# LED_Controller.net
KiCad netlist of a schematic drawn in EAGLE
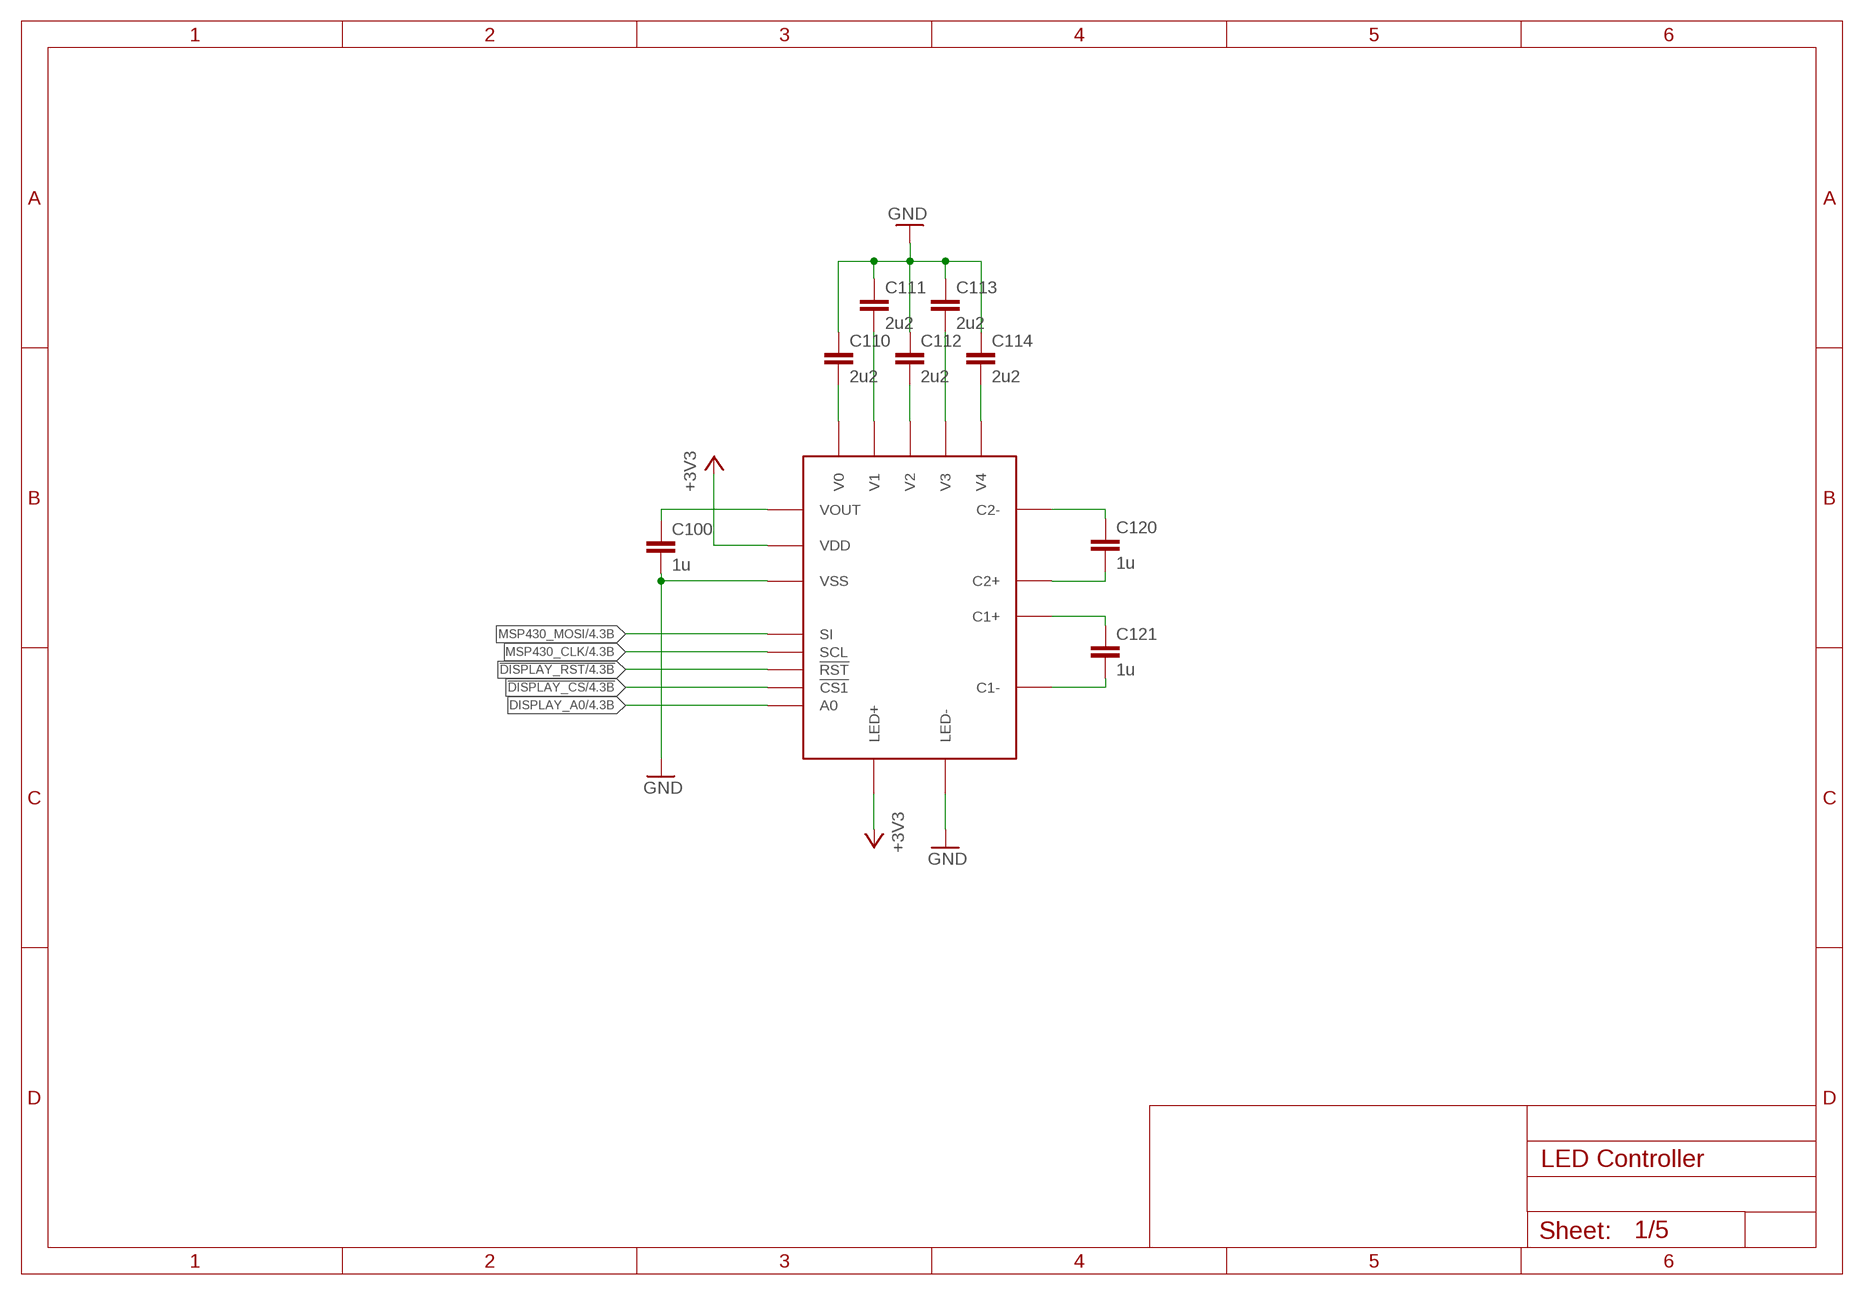
[diagram p0: schematic, sheet 1]
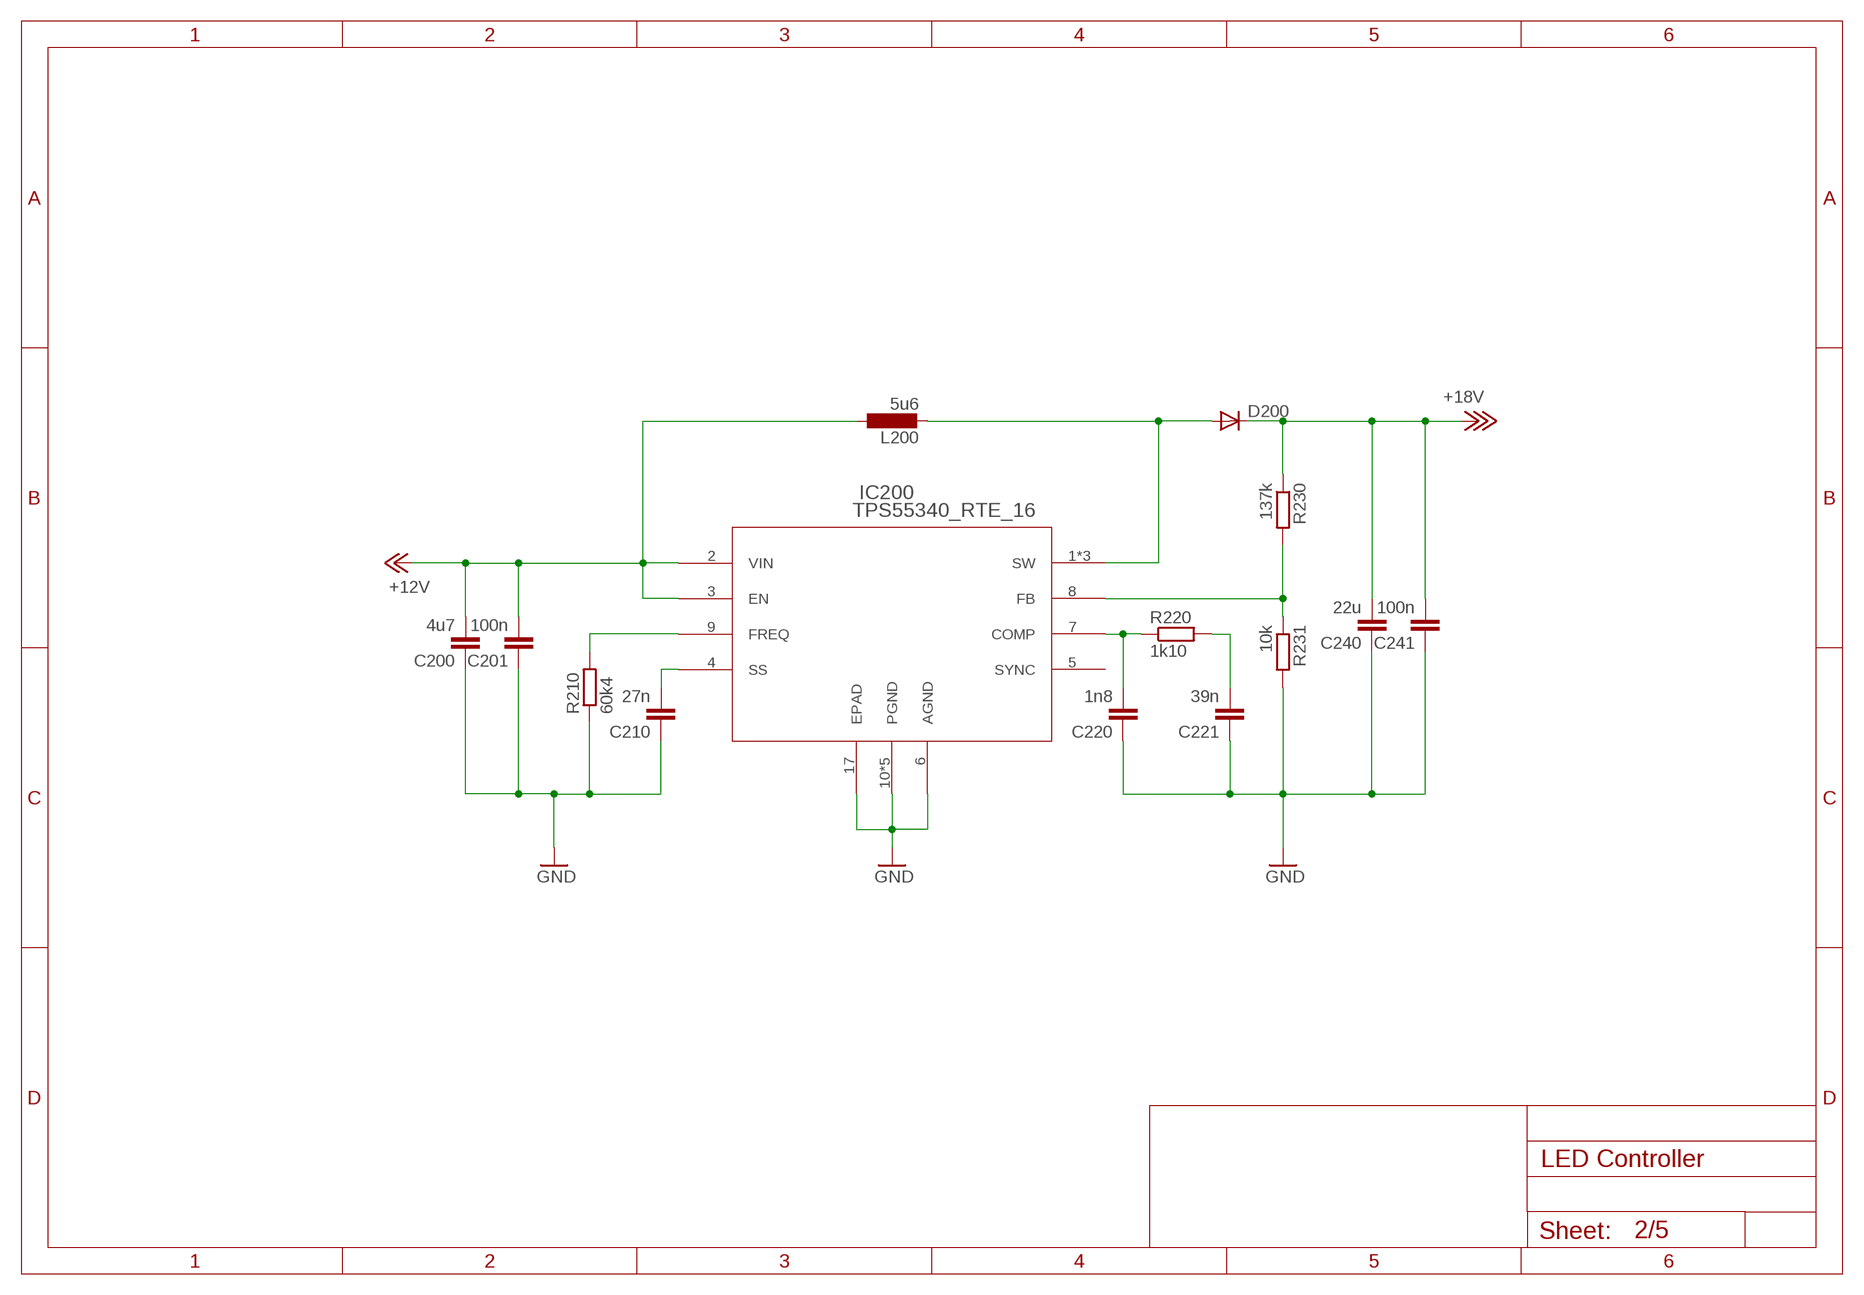
[diagram p1: schematic, sheet 2]
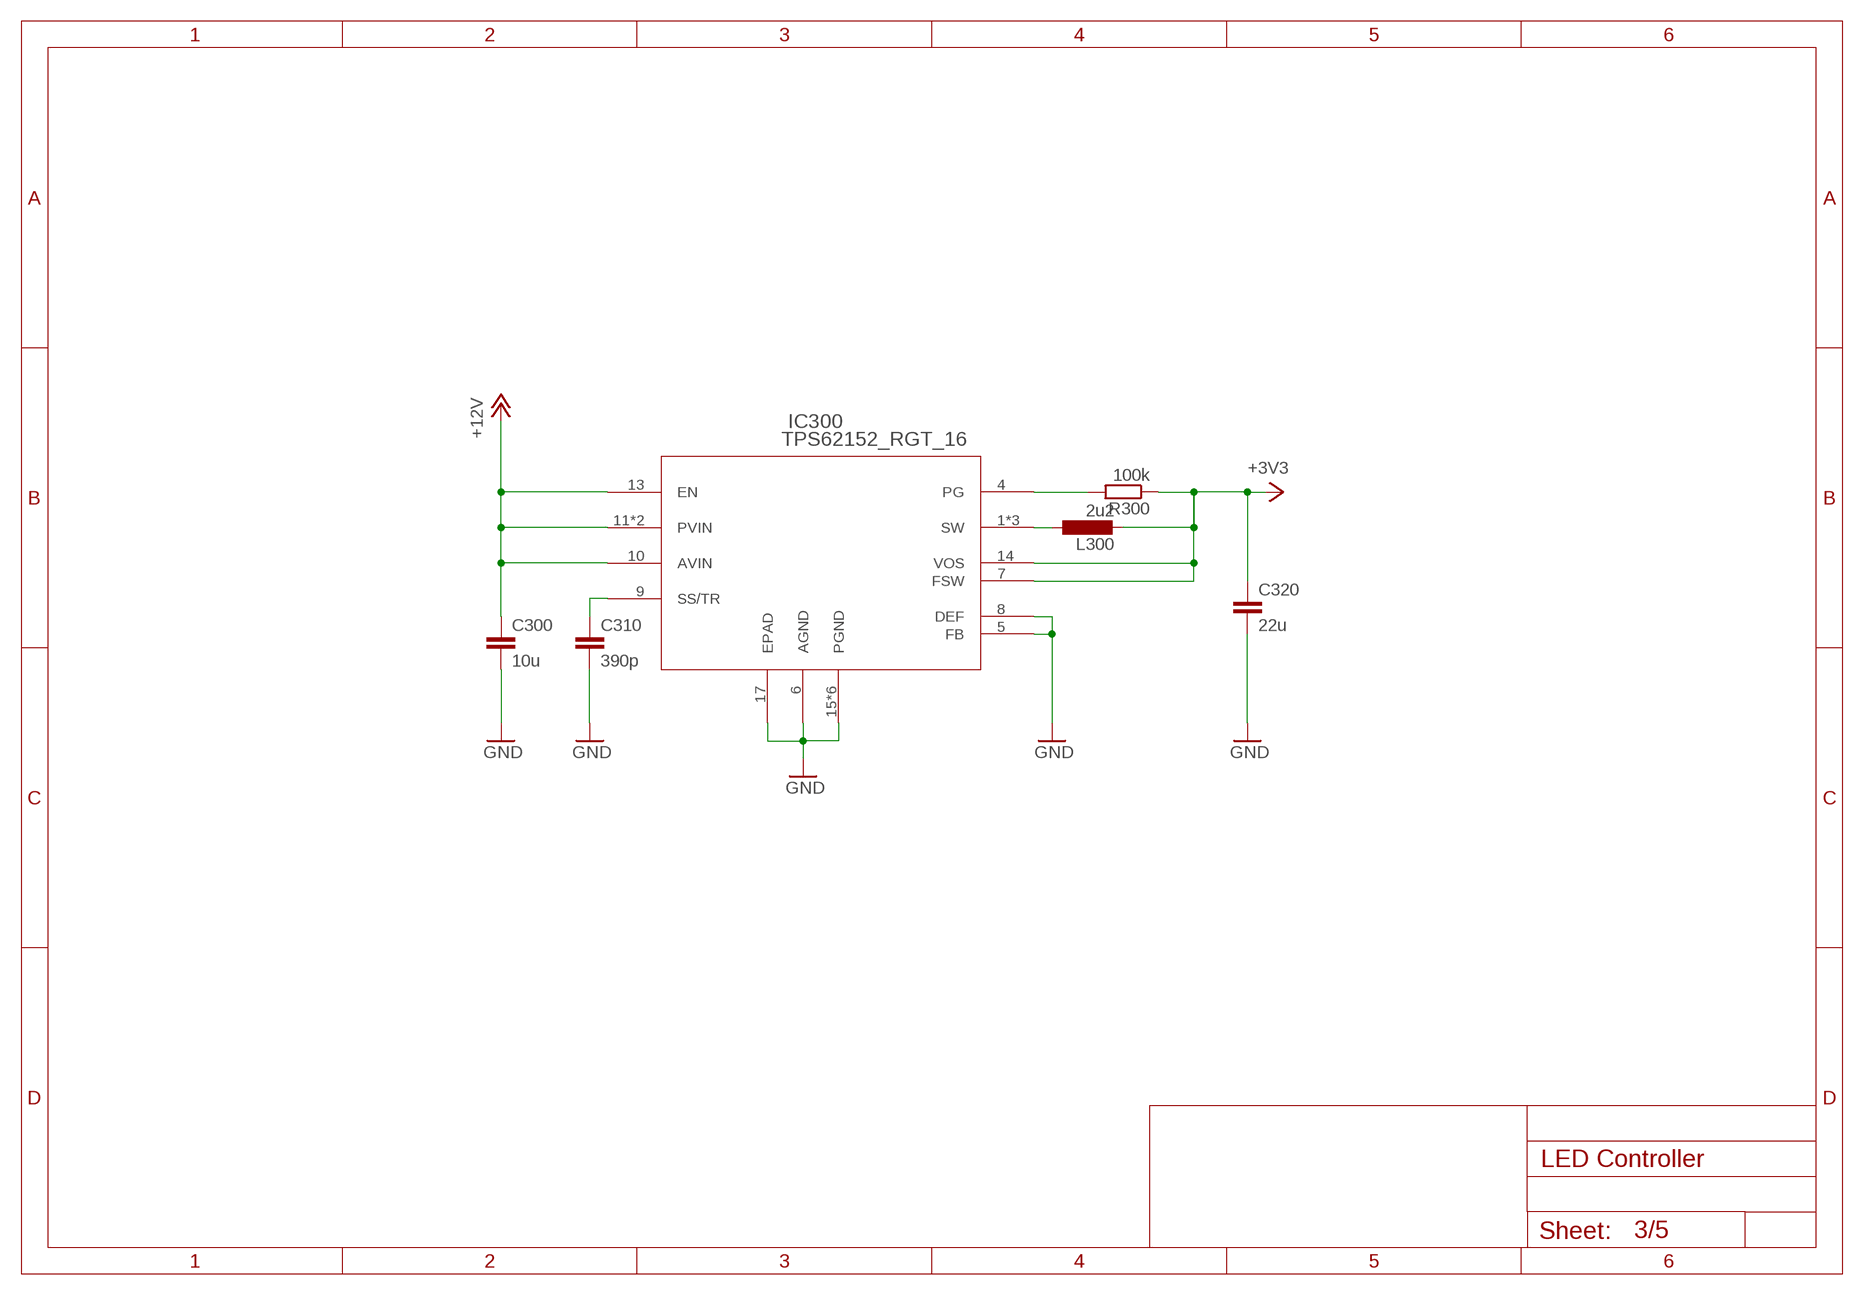
[diagram p2: schematic, sheet 3]
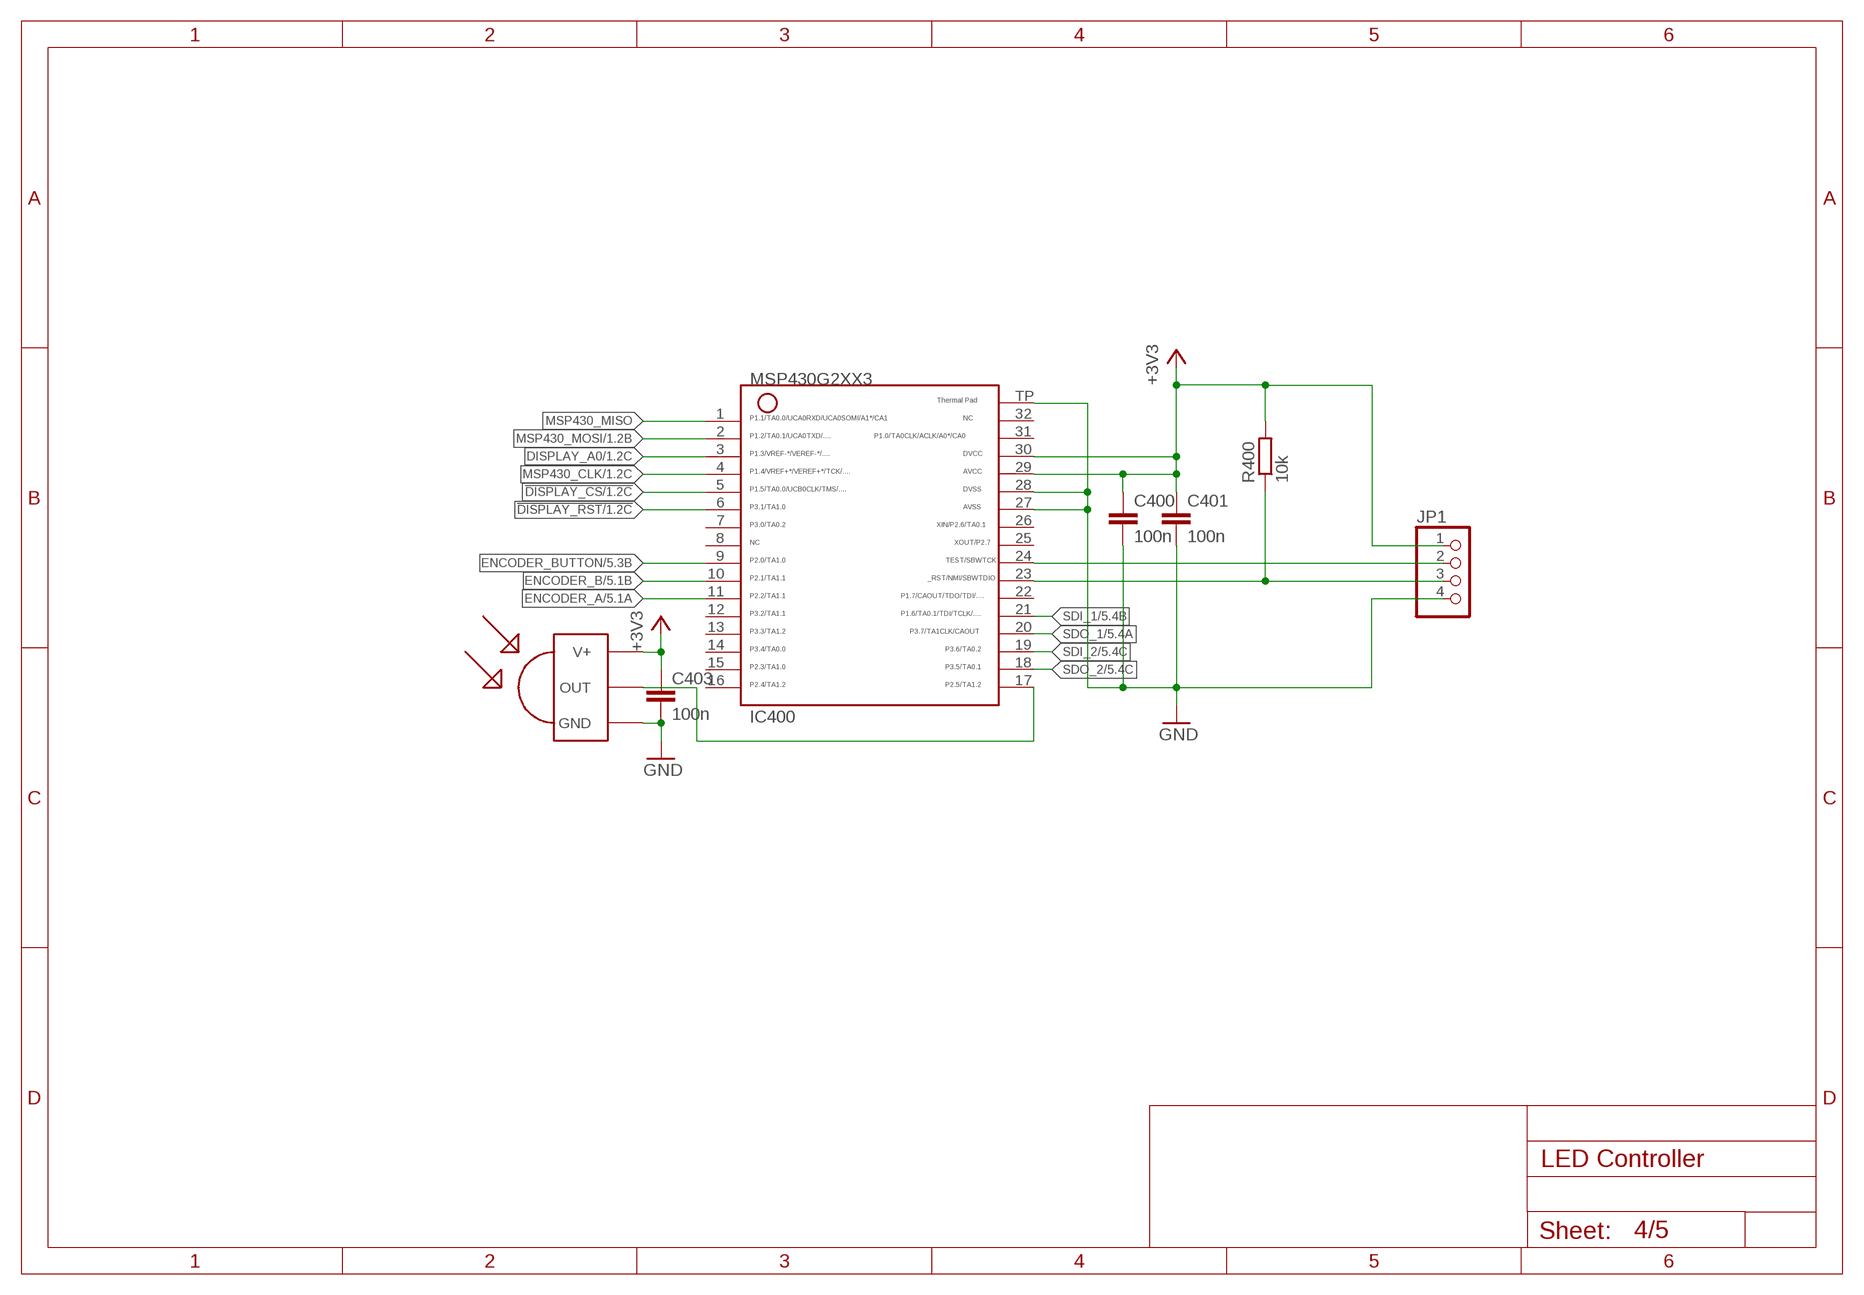
[diagram p3: schematic, sheet 4]
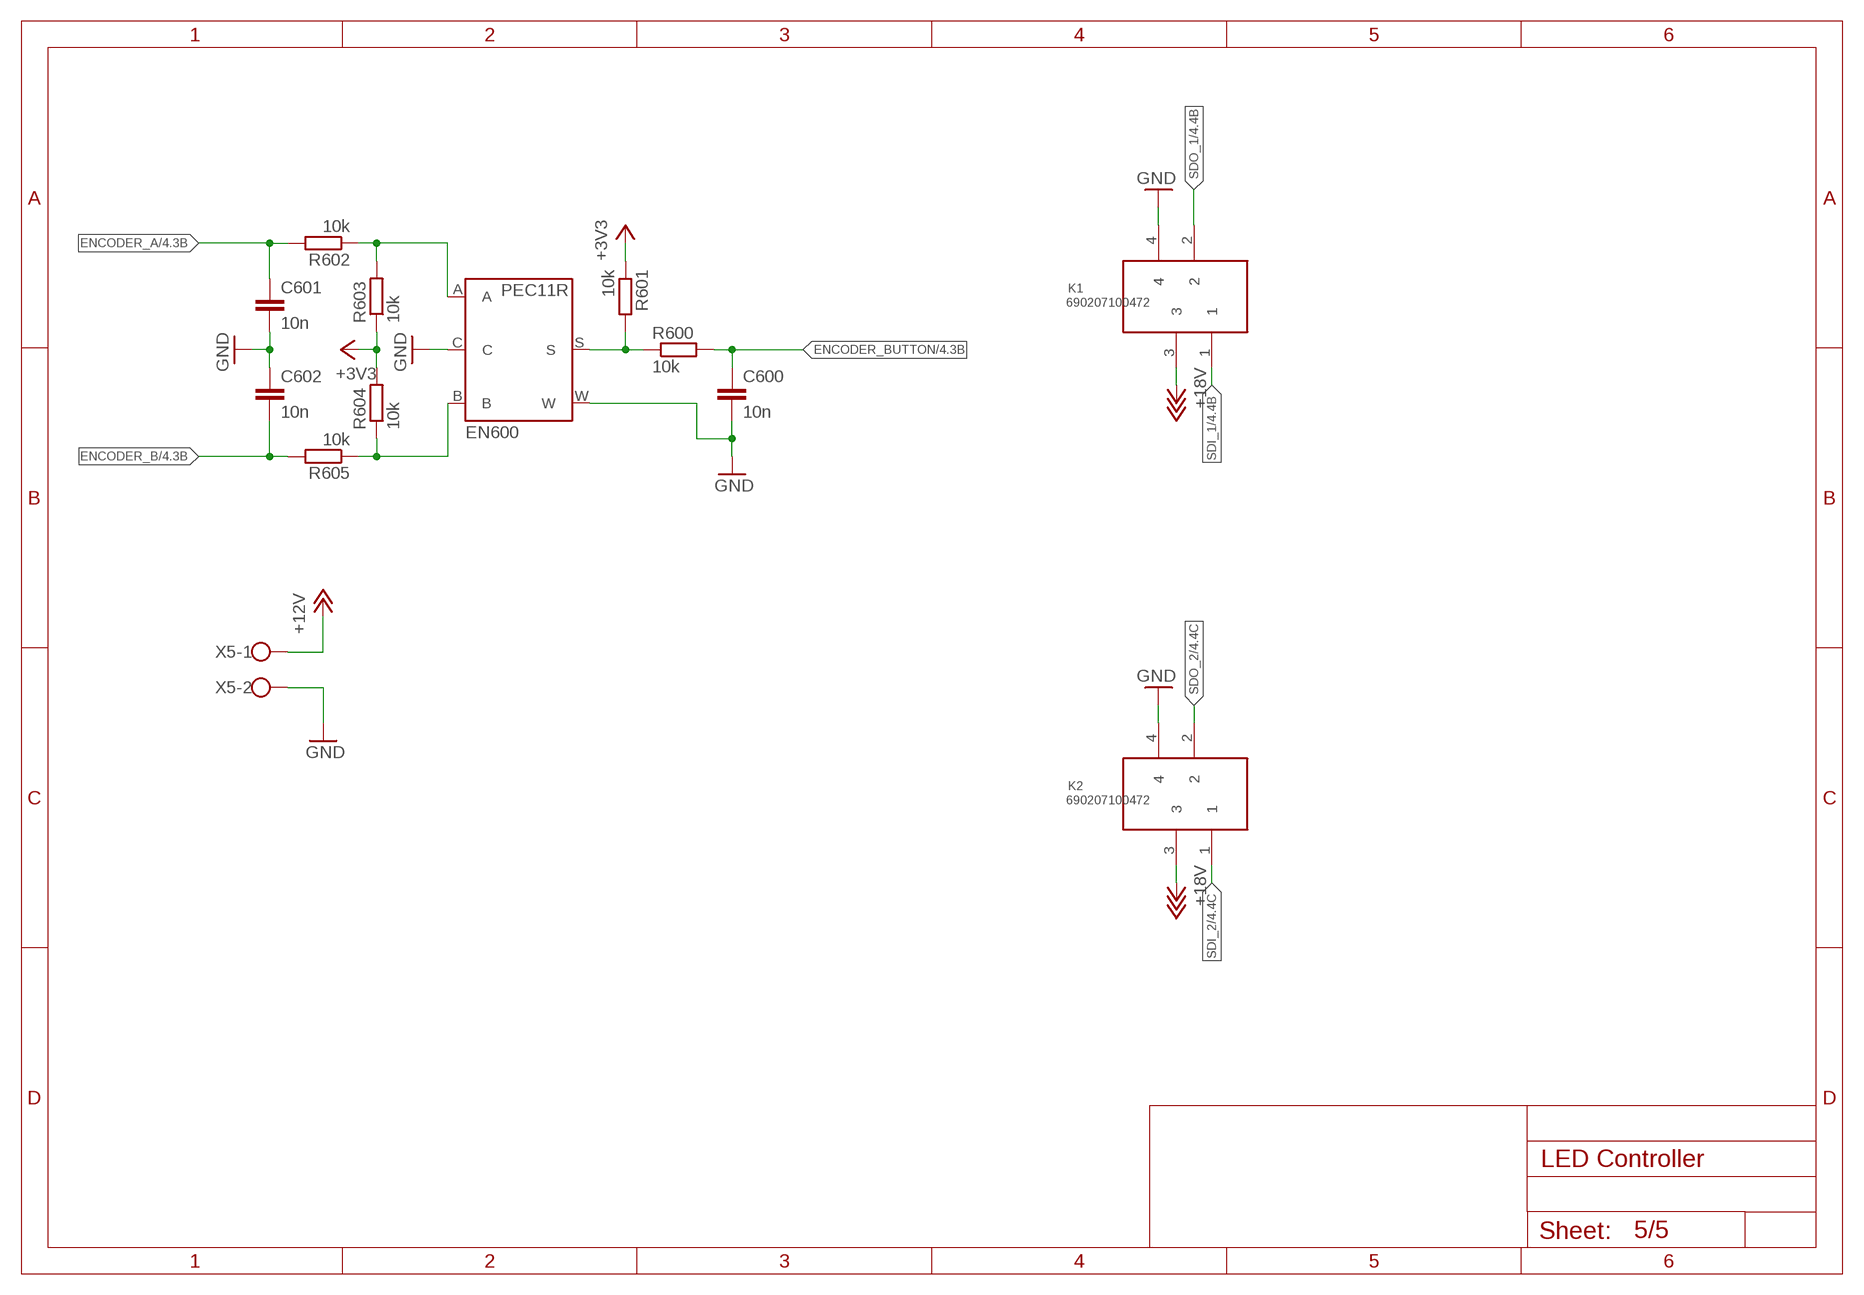
[diagram p4: schematic, sheet 5]

(export (version "E")
  (design (tool "Eeschema 10.0.6"))
  (components
    (comp (ref "C300")
      (value "10u")
      (footprint "eagle-import:C0805")
      (libsource (lib "eagle-import") (part "C-EUC0805"))
    )
    (comp (ref "C310")
      (value "390p")
      (footprint "eagle-import:C0603")
      (libsource (lib "eagle-import") (part "C-EUC0603"))
    )
    (comp (ref "C320")
      (value "22u")
      (footprint "eagle-import:C0805")
      (libsource (lib "eagle-import") (part "C-EUC0805"))
    )
    (comp (ref "IC300")
      (value "TPS62152_RGT_16")
      (footprint "eagle-import:RGT16_1P7X1P7")
      (fields
        (field (name "GENERIC_PART_NUMBER") "TPS62152")
        (field (name "MANUFACTURER") "Texas Instruments")
        (field (name "MANUFACTURER_PART_NUMBER") "tps62152_rgt_16")
      )
      (libsource (lib "eagle-import") (part "TPS62152_RGT_16"))
    )
    (comp (ref "L300")
      (value "2u2")
      (footprint "eagle-import:SDR0403")
      (libsource (lib "eagle-import") (part "L-EUSDR0403"))
    )
    (comp (ref "R300")
      (value "100k")
      (footprint "eagle-import:R0603")
      (libsource (lib "eagle-import") (part "R-EU_R0603"))
    )
    (comp (ref "C100")
      (value "1u")
      (footprint "eagle-import:C0603")
      (libsource (lib "eagle-import") (part "C-EUC0603"))
    )
    (comp (ref "C110")
      (value "2u2")
      (footprint "eagle-import:C0603")
      (libsource (lib "eagle-import") (part "C-EUC0603"))
    )
    (comp (ref "C111")
      (value "2u2")
      (footprint "eagle-import:C0603")
      (libsource (lib "eagle-import") (part "C-EUC0603"))
    )
    (comp (ref "C112")
      (value "2u2")
      (footprint "eagle-import:C0603")
      (libsource (lib "eagle-import") (part "C-EUC0603"))
    )
    (comp (ref "C113")
      (value "2u2")
      (footprint "eagle-import:C0603")
      (libsource (lib "eagle-import") (part "C-EUC0603"))
    )
    (comp (ref "C114")
      (value "2u2")
      (footprint "eagle-import:C0603")
      (libsource (lib "eagle-import") (part "C-EUC0603"))
    )
    (comp (ref "C120")
      (value "1u")
      (footprint "eagle-import:C0603")
      (libsource (lib "eagle-import") (part "C-EUC0603"))
    )
    (comp (ref "C121")
      (value "1u")
      (footprint "eagle-import:C0603")
      (libsource (lib "eagle-import") (part "C-EUC0603"))
    )
    (comp (ref "U$3")
      (value "DISPLAY")
      (footprint "eagle-import:NHD-C12832A1Z-NSW-BBW-3V3")
      (libsource (lib "eagle-import") (part "DISPLAY"))
    )
    (comp (ref "C200")
      (value "4u7")
      (footprint "eagle-import:C1206")
      (libsource (lib "eagle-import") (part "C-EUC1206"))
    )
    (comp (ref "C201")
      (value "100n")
      (footprint "eagle-import:C1206")
      (libsource (lib "eagle-import") (part "C-EUC1206"))
    )
    (comp (ref "C210")
      (value "27n")
      (footprint "eagle-import:C0603")
      (libsource (lib "eagle-import") (part "C-EUC0603"))
    )
    (comp (ref "C220")
      (value "1n8")
      (footprint "eagle-import:C0603")
      (libsource (lib "eagle-import") (part "C-EUC0603"))
    )
    (comp (ref "C221")
      (value "39n")
      (footprint "eagle-import:C0603")
      (libsource (lib "eagle-import") (part "C-EUC0603"))
    )
    (comp (ref "C240")
      (value "22u")
      (footprint "eagle-import:C1210")
      (libsource (lib "eagle-import") (part "C-EUC1210"))
    )
    (comp (ref "C241")
      (value "100n")
      (footprint "eagle-import:C1206")
      (libsource (lib "eagle-import") (part "C-EUC1206"))
    )
    (comp (ref "D200")
      (value "DIODE-SMC")
      (footprint "eagle-import:SMC")
      (libsource (lib "eagle-import") (part "DIODE-SMC"))
    )
    (comp (ref "IC200")
      (value "TPS55340_RTE_16")
      (footprint "eagle-import:RTE16")
      (fields (field (name "MANUFACTURER_PART_NUMBER") "tps55340_rte_16"))
      (libsource (lib "eagle-import") (part "TPS55340_RTE_16"))
    )
    (comp (ref "L200")
      (value "5u6")
      (footprint "eagle-import:SRP5030T")
      (libsource (lib "eagle-import") (part "L-EUSRP5030T"))
    )
    (comp (ref "R210")
      (value "60k4")
      (footprint "eagle-import:R0603")
      (libsource (lib "eagle-import") (part "R-EU_R0603"))
    )
    (comp (ref "R220")
      (value "1k10")
      (footprint "eagle-import:R0603")
      (libsource (lib "eagle-import") (part "R-EU_R0603"))
    )
    (comp (ref "R230")
      (value "137k")
      (footprint "eagle-import:R0603")
      (libsource (lib "eagle-import") (part "R-EU_R0603"))
    )
    (comp (ref "R231")
      (value "10k")
      (footprint "eagle-import:R0603")
      (libsource (lib "eagle-import") (part "R-EU_R0603"))
    )
    (comp (ref "C600")
      (value "10n")
      (footprint "eagle-import:C0603")
      (libsource (lib "eagle-import") (part "C-EUC0603"))
    )
    (comp (ref "C601")
      (value "10n")
      (footprint "eagle-import:C0603")
      (libsource (lib "eagle-import") (part "C-EUC0603"))
    )
    (comp (ref "C602")
      (value "10n")
      (footprint "eagle-import:C0603")
      (libsource (lib "eagle-import") (part "C-EUC0603"))
    )
    (comp (ref "EN600")
      (value "PEC11R")
      (footprint "eagle-import:PEC11R")
      (libsource (lib "eagle-import") (part "PEC11R"))
    )
    (comp (ref "K1")
      (value "690207100472")
      (footprint "eagle-import:690207100472")
      (libsource (lib "eagle-import") (part "690207100472"))
    )
    (comp (ref "K2")
      (value "690207100472")
      (footprint "eagle-import:690207100472")
      (libsource (lib "eagle-import") (part "690207100472"))
    )
    (comp (ref "R600")
      (value "10k")
      (footprint "eagle-import:R0603")
      (libsource (lib "eagle-import") (part "R-EU_R0603"))
    )
    (comp (ref "R601")
      (value "10k")
      (footprint "eagle-import:R0603")
      (libsource (lib "eagle-import") (part "R-EU_R0603"))
    )
    (comp (ref "R602")
      (value "10k")
      (footprint "eagle-import:R0603")
      (libsource (lib "eagle-import") (part "R-EU_R0603"))
    )
    (comp (ref "R603")
      (value "10k")
      (footprint "eagle-import:R0603")
      (libsource (lib "eagle-import") (part "R-EU_R0603"))
    )
    (comp (ref "R604")
      (value "10k")
      (footprint "eagle-import:R0603")
      (libsource (lib "eagle-import") (part "R-EU_R0603"))
    )
    (comp (ref "R605")
      (value "10k")
      (footprint "eagle-import:R0603")
      (libsource (lib "eagle-import") (part "R-EU_R0603"))
    )
    (comp (ref "X5")
      (value "W237-102")
      (footprint "eagle-import:W237-102")
      (fields (field (name "MPN") "237-102"))
      (libsource (lib "eagle-import") (part "W237-102"))
    )
    (comp (ref "C400")
      (value "100n")
      (footprint "eagle-import:C0603")
      (libsource (lib "eagle-import") (part "C-EUC0603"))
    )
    (comp (ref "C401")
      (value "100n")
      (footprint "eagle-import:C0603")
      (libsource (lib "eagle-import") (part "C-EUC0603"))
    )
    (comp (ref "C403")
      (value "100n")
      (footprint "eagle-import:C0603")
      (libsource (lib "eagle-import") (part "C-EUC0603"))
    )
    (comp (ref "IC400")
      (value "G2XX3---RHB32")
      (footprint "eagle-import:RHB32")
      (libsource (lib "eagle-import") (part "G2XX3---RHB32"))
    )
    (comp (ref "JP1")
      (value "PINHD-1X4")
      (footprint "eagle-import:1X04")
      (libsource (lib "eagle-import") (part "PINHD-1X4"))
    )
    (comp (ref "R400")
      (value "10k")
      (footprint "eagle-import:R0603")
      (libsource (lib "eagle-import") (part "R-EU_R0603"))
    )
    (comp (ref "U$1")
      (value "TSOP1738")
      (footprint "eagle-import:TSOP17XX")
      (libsource (lib "eagle-import") (part "TSOP1738"))
    )
  )
  (nets
    (net (code "1") (name "+3V3") (class "Default")
      (node (ref "C320") (pin "1") (pinfunction "1_1") (pintype "passive"))
      (node (ref "C400") (pin "1") (pinfunction "1_1") (pintype "passive"))
      (node (ref "C401") (pin "1") (pinfunction "1_1") (pintype "passive"))
      (node (ref "C403") (pin "1") (pinfunction "1_1") (pintype "passive"))
      (node (ref "IC300") (pin "14") (pinfunction "VOS_14") (pintype "input"))
      (node (ref "IC300") (pin "7") (pinfunction "FSW_7") (pintype "input"))
      (node (ref "IC400") (pin "29") (pinfunction "29_29") (pintype "bidirectional"))
      (node (ref "IC400") (pin "30") (pinfunction "30_30") (pintype "bidirectional"))
      (node (ref "JP1") (pin "1") (pinfunction "1_1") (pintype "passive"))
      (node (ref "L300") (pin "V_2") (pinfunction "2_V_2") (pintype "passive"))
      (node (ref "R300") (pin "1") (pinfunction "1_1") (pintype "passive"))
      (node (ref "R400") (pin "2") (pinfunction "2_2") (pintype "passive"))
      (node (ref "R601") (pin "1") (pinfunction "1_1") (pintype "passive"))
      (node (ref "R603") (pin "1") (pinfunction "1_1") (pintype "passive"))
      (node (ref "R604") (pin "2") (pinfunction "2_2") (pintype "passive"))
      (node (ref "U$1") (pin "V+") (pinfunction "V+_V+") (pintype "bidirectional"))
      (node (ref "U$3") (pin "A") (pinfunction "LED+_A") (pintype "passive"))
      (node (ref "U$3") (pin "P12") (pinfunction "VDD_P12") (pintype "passive"))
    )
    (net (code "2") (name "+12V") (class "Default")
      (node (ref "C200") (pin "2") (pinfunction "2_2") (pintype "passive"))
      (node (ref "C201") (pin "2") (pinfunction "2_2") (pintype "passive"))
      (node (ref "C300") (pin "1") (pinfunction "1_1") (pintype "passive"))
      (node (ref "IC200") (pin "2") (pinfunction "VIN_2") (pintype "input"))
      (node (ref "IC200") (pin "3") (pinfunction "EN_3") (pintype "passive"))
      (node (ref "IC300") (pin "10") (pinfunction "AVIN_10") (pintype "input"))
      (node (ref "IC300") (pin "11") (pinfunction "PVIN_11") (pintype "input"))
      (node (ref "IC300") (pin "12") (pinfunction "PVIN_12") (pintype "input"))
      (node (ref "IC300") (pin "13") (pinfunction "EN_13") (pintype "input"))
      (node (ref "L200") (pin "V_1") (pinfunction "1_V_1") (pintype "passive"))
      (node (ref "X5") (pin "1") (pinfunction "KL_1") (pintype "passive"))
    )
    (net (code "3") (name "+18V") (class "Default")
      (node (ref "C240") (pin "2") (pinfunction "2_2") (pintype "passive"))
      (node (ref "C241") (pin "2") (pinfunction "2_2") (pintype "passive"))
      (node (ref "D200") (pin "C") (pinfunction "C_C") (pintype "passive"))
      (node (ref "K1") (pin "3") (pinfunction "3_3") (pintype "passive"))
      (node (ref "K2") (pin "3") (pinfunction "3_3") (pintype "passive"))
      (node (ref "R230") (pin "1") (pinfunction "1_1") (pintype "passive"))
    )
    (net (code "4") (name "DISPLAY_A0") (class "Default")
      (node (ref "IC400") (pin "3") (pinfunction "3_3") (pintype "bidirectional"))
      (node (ref "U$3") (pin "P15") (pinfunction "A0_P15") (pintype "passive"))
    )
    (net (code "5") (name "ENCODER_A") (class "Default")
      (node (ref "C601") (pin "1") (pinfunction "1_1") (pintype "passive"))
      (node (ref "IC400") (pin "11") (pinfunction "11_11") (pintype "bidirectional"))
      (node (ref "R602") (pin "2") (pinfunction "2_2") (pintype "passive"))
    )
    (net (code "6") (name "ENCODER_B") (class "Default")
      (node (ref "C602") (pin "2") (pinfunction "2_2") (pintype "passive"))
      (node (ref "IC400") (pin "10") (pinfunction "10_10") (pintype "bidirectional"))
      (node (ref "R605") (pin "2") (pinfunction "2_2") (pintype "passive"))
    )
    (net (code "7") (name "ENCODER_BUTTON") (class "Default")
      (node (ref "C600") (pin "1") (pinfunction "1_1") (pintype "passive"))
      (node (ref "IC400") (pin "9") (pinfunction "9_9") (pintype "bidirectional"))
      (node (ref "R600") (pin "2") (pinfunction "2_2") (pintype "passive"))
    )
    (net (code "8") (name "GND") (class "Default")
      (node (ref "C100") (pin "2") (pinfunction "2_2") (pintype "passive"))
      (node (ref "C110") (pin "1") (pinfunction "1_1") (pintype "passive"))
      (node (ref "C111") (pin "1") (pinfunction "1_1") (pintype "passive"))
      (node (ref "C112") (pin "1") (pinfunction "1_1") (pintype "passive"))
      (node (ref "C113") (pin "1") (pinfunction "1_1") (pintype "passive"))
      (node (ref "C114") (pin "1") (pinfunction "1_1") (pintype "passive"))
      (node (ref "C200") (pin "1") (pinfunction "1_1") (pintype "passive"))
      (node (ref "C201") (pin "1") (pinfunction "1_1") (pintype "passive"))
      (node (ref "C210") (pin "1") (pinfunction "1_1") (pintype "passive"))
      (node (ref "C220") (pin "1") (pinfunction "1_1") (pintype "passive"))
      (node (ref "C221") (pin "1") (pinfunction "1_1") (pintype "passive"))
      (node (ref "C240") (pin "1") (pinfunction "1_1") (pintype "passive"))
      (node (ref "C241") (pin "1") (pinfunction "1_1") (pintype "passive"))
      (node (ref "C300") (pin "2") (pinfunction "2_2") (pintype "passive"))
      (node (ref "C310") (pin "2") (pinfunction "2_2") (pintype "passive"))
      (node (ref "C320") (pin "2") (pinfunction "2_2") (pintype "passive"))
      (node (ref "C400") (pin "2") (pinfunction "2_2") (pintype "passive"))
      (node (ref "C401") (pin "2") (pinfunction "2_2") (pintype "passive"))
      (node (ref "C403") (pin "2") (pinfunction "2_2") (pintype "passive"))
      (node (ref "C600") (pin "2") (pinfunction "2_2") (pintype "passive"))
      (node (ref "C601") (pin "2") (pinfunction "2_2") (pintype "passive"))
      (node (ref "C602") (pin "1") (pinfunction "1_1") (pintype "passive"))
      (node (ref "EN600") (pin "C") (pinfunction "C_C") (pintype "bidirectional"))
      (node (ref "EN600") (pin "W") (pinfunction "W_W") (pintype "bidirectional"))
      (node (ref "IC200") (pin "10") (pinfunction "PGND_10") (pintype "power_in"))
      (node (ref "IC200") (pin "11") (pinfunction "PGND_11") (pintype "power_in"))
      (node (ref "IC200") (pin "12") (pinfunction "PGND_12") (pintype "power_in"))
      (node (ref "IC200") (pin "13") (pinfunction "PGND_13") (pintype "power_in"))
      (node (ref "IC200") (pin "14") (pinfunction "PGND_14") (pintype "power_in"))
      (node (ref "IC200") (pin "17") (pinfunction "EPAD_17") (pintype "passive"))
      (node (ref "IC200") (pin "6") (pinfunction "AGND_6") (pintype "power_in"))
      (node (ref "IC300") (pin "15") (pinfunction "PGND_15") (pintype "power_in"))
      (node (ref "IC300") (pin "16") (pinfunction "PGND_16") (pintype "power_in"))
      (node (ref "IC300") (pin "17") (pinfunction "EPAD_17") (pintype "passive"))
      (node (ref "IC300") (pin "5") (pinfunction "FB_5") (pintype "input"))
      (node (ref "IC300") (pin "6") (pinfunction "AGND_6") (pintype "power_in"))
      (node (ref "IC300") (pin "8") (pinfunction "DEF_8") (pintype "input"))
      (node (ref "IC300") (pin "V") (pinfunction "PGND_V") (pintype "power_in"))
      (node (ref "IC300") (pin "V_1") (pinfunction "PGND_V_1") (pintype "power_in"))
      (node (ref "IC300") (pin "V_2") (pinfunction "PGND_V_2") (pintype "power_in"))
      (node (ref "IC300") (pin "V_3") (pinfunction "PGND_V_3") (pintype "power_in"))
      (node (ref "IC400") (pin "27") (pinfunction "27_27") (pintype "bidirectional"))
      (node (ref "IC400") (pin "28") (pinfunction "28_28") (pintype "bidirectional"))
      (node (ref "IC400") (pin "TP") (pinfunction "TP_TP") (pintype "bidirectional"))
      (node (ref "JP1") (pin "4") (pinfunction "4_4") (pintype "passive"))
      (node (ref "K1") (pin "4") (pinfunction "4_4") (pintype "passive"))
      (node (ref "K2") (pin "4") (pinfunction "4_4") (pintype "passive"))
      (node (ref "R210") (pin "1") (pinfunction "1_1") (pintype "passive"))
      (node (ref "R231") (pin "2") (pinfunction "2_2") (pintype "passive"))
      (node (ref "U$1") (pin "GND") (pinfunction "GND_GND") (pintype "bidirectional"))
      (node (ref "U$3") (pin "K") (pinfunction "LED-_K") (pintype "passive"))
      (node (ref "U$3") (pin "P11") (pinfunction "VSS_P11") (pintype "passive"))
      (node (ref "X5") (pin "2") (pinfunction "KL_2") (pintype "passive"))
    )
    (net (code "9") (name "MSP430_CLK") (class "Default")
      (node (ref "IC400") (pin "4") (pinfunction "4_4") (pintype "bidirectional"))
      (node (ref "U$3") (pin "P14") (pinfunction "SCL_P14") (pintype "passive"))
    )
    (net (code "10") (name "MSP430_MISO") (class "Default")
      (node (ref "IC400") (pin "1") (pinfunction "1_1") (pintype "bidirectional"))
    )
    (net (code "11") (name "MSP430_MOSI") (class "Default")
      (node (ref "IC400") (pin "2") (pinfunction "2_2") (pintype "bidirectional"))
      (node (ref "U$3") (pin "P13") (pinfunction "SI_P13") (pintype "passive"))
    )
    (net (code "12") (name "Net-(C221-Pad2)") (class "Default")
      (node (ref "C221") (pin "2") (pinfunction "2_2") (pintype "passive"))
      (node (ref "R220") (pin "2") (pinfunction "2_2") (pintype "passive"))
    )
    (net (code "13") (name "Net-(EN600-PadA)") (class "Default")
      (node (ref "EN600") (pin "A") (pinfunction "A_A") (pintype "bidirectional"))
      (node (ref "R602") (pin "1") (pinfunction "1_1") (pintype "passive"))
      (node (ref "R603") (pin "2") (pinfunction "2_2") (pintype "passive"))
    )
    (net (code "14") (name "Net-(EN600-PadB)") (class "Default")
      (node (ref "EN600") (pin "B") (pinfunction "B_B") (pintype "bidirectional"))
      (node (ref "R604") (pin "1") (pinfunction "1_1") (pintype "passive"))
      (node (ref "R605") (pin "1") (pinfunction "1_1") (pintype "passive"))
    )
    (net (code "15") (name "Net-(EN600-PadS)") (class "Default")
      (node (ref "EN600") (pin "S") (pinfunction "S_S") (pintype "bidirectional"))
      (node (ref "R600") (pin "1") (pinfunction "1_1") (pintype "passive"))
      (node (ref "R601") (pin "2") (pinfunction "2_2") (pintype "passive"))
    )
    (net (code "16") (name "Net-(IC200-COMP)") (class "Default")
      (node (ref "C220") (pin "2") (pinfunction "2_2") (pintype "passive"))
      (node (ref "IC200") (pin "7") (pinfunction "COMP_7") (pintype "passive"))
      (node (ref "R220") (pin "1") (pinfunction "1_1") (pintype "passive"))
    )
    (net (code "17") (name "Net-(IC200-FB)") (class "Default")
      (node (ref "IC200") (pin "8") (pinfunction "FB_8") (pintype "passive"))
      (node (ref "R230") (pin "2") (pinfunction "2_2") (pintype "passive"))
      (node (ref "R231") (pin "1") (pinfunction "1_1") (pintype "passive"))
    )
    (net (code "18") (name "Net-(IC200-FREQ)") (class "Default")
      (node (ref "IC200") (pin "9") (pinfunction "FREQ_9") (pintype "passive"))
      (node (ref "R210") (pin "2") (pinfunction "2_2") (pintype "passive"))
    )
    (net (code "19") (name "Net-(IC200-SS)") (class "Default")
      (node (ref "C210") (pin "2") (pinfunction "2_2") (pintype "passive"))
      (node (ref "IC200") (pin "4") (pinfunction "SS_4") (pintype "passive"))
    )
    (net (code "20") (name "Net-(IC300-PG)") (class "Default")
      (node (ref "IC300") (pin "4") (pinfunction "PG_4") (pintype "output"))
      (node (ref "R300") (pin "2") (pinfunction "2_2") (pintype "passive"))
    )
    (net (code "21") (name "Net-(IC300-SS{slash}TR)") (class "Default")
      (node (ref "C310") (pin "1") (pinfunction "1_1") (pintype "passive"))
      (node (ref "IC300") (pin "9") (pinfunction "SS/TR_9") (pintype "input"))
    )
    (net (code "22") (name "Net-(IC400-Pad17)") (class "Default")
      (node (ref "IC400") (pin "17") (pinfunction "17_17") (pintype "bidirectional"))
      (node (ref "U$1") (pin "OUT") (pinfunction "OUT_OUT") (pintype "bidirectional"))
    )
    (net (code "23") (name "Net-(IC400-Pad23)") (class "Default")
      (node (ref "IC400") (pin "23") (pinfunction "23_23") (pintype "bidirectional"))
      (node (ref "JP1") (pin "3") (pinfunction "3_3") (pintype "passive"))
      (node (ref "R400") (pin "1") (pinfunction "1_1") (pintype "passive"))
    )
    (net (code "24") (name "Net-(IC400-Pad24)") (class "Default")
      (node (ref "IC400") (pin "24") (pinfunction "24_24") (pintype "bidirectional"))
      (node (ref "JP1") (pin "2") (pinfunction "2_2") (pintype "passive"))
    )
    (net (code "25") (name "Net-(L200-2)") (class "Default")
      (node (ref "D200") (pin "A") (pinfunction "A_A") (pintype "passive"))
      (node (ref "IC200") (pin "1") (pinfunction "SW_1") (pintype "passive"))
      (node (ref "IC200") (pin "15") (pinfunction "SW_15") (pintype "passive"))
      (node (ref "IC200") (pin "16") (pinfunction "SW_16") (pintype "passive"))
      (node (ref "L200") (pin "V_2") (pinfunction "2_V_2") (pintype "passive"))
    )
    (net (code "26") (name "Net-(L300-1)") (class "Default")
      (node (ref "IC300") (pin "1") (pinfunction "SW_1") (pintype "output"))
      (node (ref "IC300") (pin "2") (pinfunction "SW_2") (pintype "output"))
      (node (ref "IC300") (pin "3") (pinfunction "SW_3") (pintype "output"))
      (node (ref "L300") (pin "V_1") (pinfunction "1_V_1") (pintype "passive"))
    )
    (net (code "27") (name "Net-(U$3-C1+)") (class "Default")
      (node (ref "C121") (pin "1") (pinfunction "1_1") (pintype "passive"))
      (node (ref "U$3") (pin "P8") (pinfunction "C1+_P8") (pintype "passive"))
    )
    (net (code "28") (name "Net-(U$3-C1-)") (class "Default")
      (node (ref "C121") (pin "2") (pinfunction "2_2") (pintype "passive"))
      (node (ref "U$3") (pin "P9") (pinfunction "C1-_P9") (pintype "passive"))
    )
    (net (code "29") (name "Net-(U$3-C2+)") (class "Default")
      (node (ref "C120") (pin "2") (pinfunction "2_2") (pintype "passive"))
      (node (ref "U$3") (pin "P7") (pinfunction "C2+_P7") (pintype "passive"))
    )
    (net (code "30") (name "Net-(U$3-C2-)") (class "Default")
      (node (ref "C120") (pin "1") (pinfunction "1_1") (pintype "passive"))
      (node (ref "U$3") (pin "P6") (pinfunction "C2-_P6") (pintype "passive"))
    )
    (net (code "31") (name "Net-(U$3-V0)") (class "Default")
      (node (ref "C110") (pin "2") (pinfunction "2_2") (pintype "passive"))
      (node (ref "U$3") (pin "P1") (pinfunction "V0_P1") (pintype "passive"))
    )
    (net (code "32") (name "Net-(U$3-V1)") (class "Default")
      (node (ref "C111") (pin "2") (pinfunction "2_2") (pintype "passive"))
      (node (ref "U$3") (pin "P2") (pinfunction "V1_P2") (pintype "passive"))
    )
    (net (code "33") (name "Net-(U$3-V2)") (class "Default")
      (node (ref "C112") (pin "2") (pinfunction "2_2") (pintype "passive"))
      (node (ref "U$3") (pin "P3") (pinfunction "V2_P3") (pintype "passive"))
    )
    (net (code "34") (name "Net-(U$3-V3)") (class "Default")
      (node (ref "C113") (pin "2") (pinfunction "2_2") (pintype "passive"))
      (node (ref "U$3") (pin "P4") (pinfunction "V3_P4") (pintype "passive"))
    )
    (net (code "35") (name "Net-(U$3-V4)") (class "Default")
      (node (ref "C114") (pin "2") (pinfunction "2_2") (pintype "passive"))
      (node (ref "U$3") (pin "P5") (pinfunction "V4_P5") (pintype "passive"))
    )
    (net (code "36") (name "Net-(U$3-VOUT)") (class "Default")
      (node (ref "C100") (pin "1") (pinfunction "1_1") (pintype "passive"))
      (node (ref "U$3") (pin "P10") (pinfunction "VOUT_P10") (pintype "passive"))
    )
    (net (code "37") (name "SDI_1") (class "Default")
      (node (ref "IC400") (pin "21") (pinfunction "21_21") (pintype "bidirectional"))
      (node (ref "K1") (pin "1") (pinfunction "1_1") (pintype "passive"))
    )
    (net (code "38") (name "SDI_2") (class "Default")
      (node (ref "IC400") (pin "19") (pinfunction "19_19") (pintype "bidirectional"))
      (node (ref "K2") (pin "1") (pinfunction "1_1") (pintype "passive"))
    )
    (net (code "39") (name "SDO_1") (class "Default")
      (node (ref "IC400") (pin "20") (pinfunction "20_20") (pintype "bidirectional"))
      (node (ref "K1") (pin "2") (pinfunction "2_2") (pintype "passive"))
    )
    (net (code "40") (name "SDO_2") (class "Default")
      (node (ref "IC400") (pin "18") (pinfunction "18_18") (pintype "bidirectional"))
      (node (ref "K2") (pin "2") (pinfunction "2_2") (pintype "passive"))
    )
    (net (code "41") (name "unconnected-(IC200-SYNC-Pad5)") (class "Default")
      (node (ref "IC200") (pin "5") (pinfunction "SYNC_5") (pintype "passive"))
    )
    (net (code "42") (name "unconnected-(IC400-Pad7)") (class "Default")
      (node (ref "IC400") (pin "7") (pinfunction "7_7") (pintype "bidirectional"))
    )
    (net (code "43") (name "unconnected-(IC400-Pad8)") (class "Default")
      (node (ref "IC400") (pin "8") (pinfunction "8_8") (pintype "bidirectional"))
    )
    (net (code "44") (name "unconnected-(IC400-Pad12)") (class "Default")
      (node (ref "IC400") (pin "12") (pinfunction "12_12") (pintype "bidirectional"))
    )
    (net (code "45") (name "unconnected-(IC400-Pad13)") (class "Default")
      (node (ref "IC400") (pin "13") (pinfunction "13_13") (pintype "bidirectional"))
    )
    (net (code "46") (name "unconnected-(IC400-Pad14)") (class "Default")
      (node (ref "IC400") (pin "14") (pinfunction "14_14") (pintype "bidirectional"))
    )
    (net (code "47") (name "unconnected-(IC400-Pad15)") (class "Default")
      (node (ref "IC400") (pin "15") (pinfunction "15_15") (pintype "bidirectional"))
    )
    (net (code "48") (name "unconnected-(IC400-Pad16)") (class "Default")
      (node (ref "IC400") (pin "16") (pinfunction "16_16") (pintype "bidirectional"))
    )
    (net (code "49") (name "unconnected-(IC400-Pad22)") (class "Default")
      (node (ref "IC400") (pin "22") (pinfunction "22_22") (pintype "bidirectional"))
    )
    (net (code "50") (name "unconnected-(IC400-Pad25)") (class "Default")
      (node (ref "IC400") (pin "25") (pinfunction "25_25") (pintype "bidirectional"))
    )
    (net (code "51") (name "unconnected-(IC400-Pad26)") (class "Default")
      (node (ref "IC400") (pin "26") (pinfunction "26_26") (pintype "bidirectional"))
    )
    (net (code "52") (name "unconnected-(IC400-Pad31)") (class "Default")
      (node (ref "IC400") (pin "31") (pinfunction "31_31") (pintype "bidirectional"))
    )
    (net (code "53") (name "unconnected-(IC400-Pad32)") (class "Default")
      (node (ref "IC400") (pin "32") (pinfunction "32_32") (pintype "bidirectional"))
    )
    (net (code "54") (name "~{DISPLAY_CS}") (class "Default")
      (node (ref "IC400") (pin "5") (pinfunction "5_5") (pintype "bidirectional"))
      (node (ref "U$3") (pin "P17") (pinfunction "~{CS1}_P17") (pintype "passive"))
    )
    (net (code "55") (name "~{DISPLAY_RST}") (class "Default")
      (node (ref "IC400") (pin "6") (pinfunction "6_6") (pintype "bidirectional"))
      (node (ref "U$3") (pin "P16") (pinfunction "~{RST}_P16") (pintype "passive"))
    )
  )
)
